# LVDS_CMOS_LVDT41v3.net
KiCad netlist of a schematic drawn in EAGLE
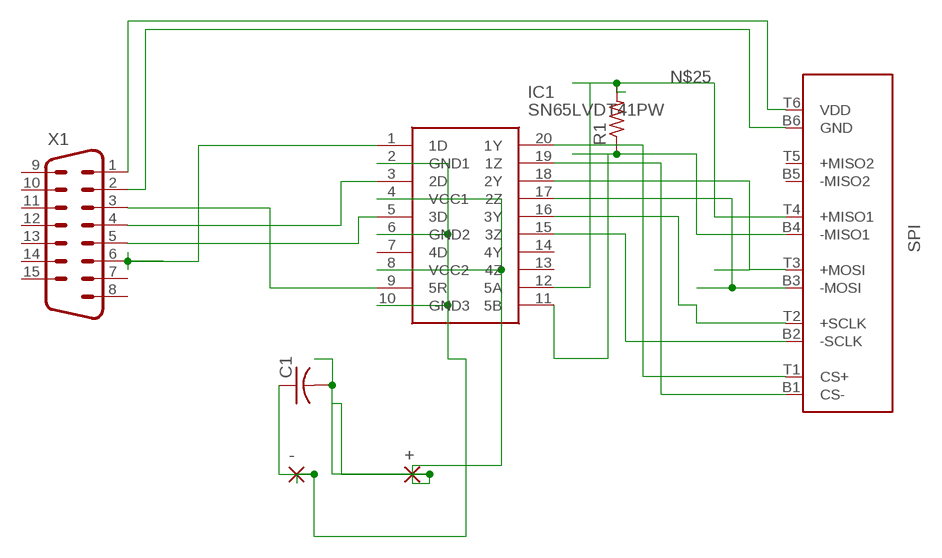
[diagram p0: schematic, sheet 1]

(export (version "E")
  (design (tool "Eeschema 10.0.6"))
  (components
    (comp (ref "+")
      (value "3,17/1,3")
      (footprint "eagle-import:3,17_1,3")
      (libsource (lib "eagle-import") (part "3,17/1,3"))
    )
    (comp (ref "-")
      (value "3,17/1,3")
      (footprint "eagle-import:3,17_1,3")
      (libsource (lib "eagle-import") (part "3,17/1,3"))
    )
    (comp (ref "C1")
      (value "C-USC0805")
      (footprint "eagle-import:C0805")
      (libsource (lib "eagle-import") (part "C-USC0805"))
    )
    (comp (ref "IC1")
      (value "SN65LVDT41PW")
      (footprint "eagle-import:SOP65P640X120-20N")
      (fields (field (name "RS_PART_NUMBER") "1625262"))
      (libsource (lib "eagle-import") (part "SN65LVDT41PW"))
    )
    (comp (ref "R1")
      (value "R-US_R0603")
      (footprint "eagle-import:R0603")
      (libsource (lib "eagle-import") (part "R-US_R0603"))
    )
    (comp (ref "SPI")
      (value "SPI")
      (footprint "eagle-import:OMNETICS_PZN-12-AA-UPDATED")
      (libsource (lib "eagle-import") (part "OMNETICS-CONNECTOR-SLAVE-SIDE"))
    )
    (comp (ref "X1")
      (value "M15H")
      (footprint "eagle-import:M15H")
      (libsource (lib "eagle-import") (part "M15H"))
    )
  )
  (nets
    (net (code "1") (name "/N$25") (class "Default")
      (node (ref "IC1") (pin "12") (pinfunction "5A_12") (pintype "input"))
      (node (ref "R1") (pin "2") (pinfunction "2_2") (pintype "passive"))
      (node (ref "SPI") (pin "T4") (pinfunction "+MISO1_T4") (pintype "bidirectional"))
    )
    (net (code "2") (name "Net-(+-P)") (class "Default")
      (node (ref "+") (pin "1") (pinfunction "P_1") (pintype "passive"))
      (node (ref "C1") (pin "2") (pinfunction "2_2") (pintype "passive"))
      (node (ref "IC1") (pin "4") (pinfunction "VCC1_4") (pintype "power_in"))
      (node (ref "IC1") (pin "8") (pinfunction "VCC2_8") (pintype "power_in"))
    )
    (net (code "3") (name "Net-(--P)") (class "Default")
      (node (ref "-") (pin "1") (pinfunction "P_1") (pintype "passive"))
      (node (ref "C1") (pin "1") (pinfunction "1_1") (pintype "passive"))
      (node (ref "IC1") (pin "10") (pinfunction "GND3_10") (pintype "power_in"))
      (node (ref "IC1") (pin "2") (pinfunction "GND1_2") (pintype "power_in"))
      (node (ref "IC1") (pin "6") (pinfunction "GND2_6") (pintype "power_in"))
    )
    (net (code "4") (name "Net-(IC1-1D)") (class "Default")
      (node (ref "IC1") (pin "1") (pinfunction "1D_1") (pintype "input"))
      (node (ref "X1") (pin "6") (pinfunction "6_6") (pintype "passive"))
    )
    (net (code "5") (name "Net-(IC1-1Y)") (class "Default")
      (node (ref "IC1") (pin "20") (pinfunction "1Y_20") (pintype "output"))
      (node (ref "SPI") (pin "T1") (pinfunction "CS+_T1") (pintype "bidirectional"))
    )
    (net (code "6") (name "Net-(IC1-1Z)") (class "Default")
      (node (ref "IC1") (pin "19") (pinfunction "1Z_19") (pintype "output"))
      (node (ref "SPI") (pin "B1") (pinfunction "CS-_B1") (pintype "bidirectional"))
    )
    (net (code "7") (name "Net-(IC1-2D)") (class "Default")
      (node (ref "IC1") (pin "3") (pinfunction "2D_3") (pintype "input"))
      (node (ref "X1") (pin "4") (pinfunction "4_4") (pintype "passive"))
    )
    (net (code "8") (name "Net-(IC1-2Y)") (class "Default")
      (node (ref "IC1") (pin "18") (pinfunction "2Y_18") (pintype "output"))
      (node (ref "SPI") (pin "T3") (pinfunction "+MOSI_T3") (pintype "bidirectional"))
    )
    (net (code "9") (name "Net-(IC1-2Z)") (class "Default")
      (node (ref "IC1") (pin "17") (pinfunction "2Z_17") (pintype "output"))
      (node (ref "SPI") (pin "B3") (pinfunction "-MOSI_B3") (pintype "bidirectional"))
    )
    (net (code "10") (name "Net-(IC1-3D)") (class "Default")
      (node (ref "IC1") (pin "5") (pinfunction "3D_5") (pintype "input"))
      (node (ref "X1") (pin "5") (pinfunction "5_5") (pintype "passive"))
    )
    (net (code "11") (name "Net-(IC1-3Y)") (class "Default")
      (node (ref "IC1") (pin "16") (pinfunction "3Y_16") (pintype "output"))
      (node (ref "SPI") (pin "T2") (pinfunction "+SCLK_T2") (pintype "bidirectional"))
    )
    (net (code "12") (name "Net-(IC1-3Z)") (class "Default")
      (node (ref "IC1") (pin "15") (pinfunction "3Z_15") (pintype "output"))
      (node (ref "SPI") (pin "B2") (pinfunction "-SCLK_B2") (pintype "bidirectional"))
    )
    (net (code "13") (name "Net-(IC1-5B)") (class "Default")
      (node (ref "IC1") (pin "11") (pinfunction "5B_11") (pintype "input"))
      (node (ref "R1") (pin "1") (pinfunction "1_1") (pintype "passive"))
      (node (ref "SPI") (pin "B4") (pinfunction "-MISO1_B4") (pintype "bidirectional"))
    )
    (net (code "14") (name "Net-(IC1-5R)") (class "Default")
      (node (ref "IC1") (pin "9") (pinfunction "5R_9") (pintype "output"))
      (node (ref "X1") (pin "3") (pinfunction "3_3") (pintype "passive"))
    )
    (net (code "15") (name "Net-(SPI-GND)") (class "Default")
      (node (ref "SPI") (pin "B6") (pinfunction "GND_B6") (pintype "bidirectional"))
      (node (ref "X1") (pin "2") (pinfunction "2_2") (pintype "passive"))
    )
    (net (code "16") (name "Net-(SPI-VDD)") (class "Default")
      (node (ref "SPI") (pin "T6") (pinfunction "VDD_T6") (pintype "bidirectional"))
      (node (ref "X1") (pin "1") (pinfunction "1_1") (pintype "passive"))
    )
    (net (code "17") (name "unconnected-(IC1-4D-Pad7)") (class "Default")
      (node (ref "IC1") (pin "7") (pinfunction "4D_7") (pintype "input"))
    )
    (net (code "18") (name "unconnected-(IC1-4Y-Pad14)") (class "Default")
      (node (ref "IC1") (pin "14") (pinfunction "4Y_14") (pintype "output"))
    )
    (net (code "19") (name "unconnected-(IC1-4Z-Pad13)") (class "Default")
      (node (ref "IC1") (pin "13") (pinfunction "4Z_13") (pintype "output"))
    )
    (net (code "20") (name "unconnected-(SPI-+MISO2-PadT5)") (class "Default")
      (node (ref "SPI") (pin "T5") (pinfunction "+MISO2_T5") (pintype "bidirectional"))
    )
    (net (code "21") (name "unconnected-(SPI--MISO2-PadB5)") (class "Default")
      (node (ref "SPI") (pin "B5") (pinfunction "-MISO2_B5") (pintype "bidirectional"))
    )
    (net (code "22") (name "unconnected-(X1-Pad7)") (class "Default")
      (node (ref "X1") (pin "7") (pinfunction "7_7") (pintype "passive"))
    )
    (net (code "23") (name "unconnected-(X1-Pad8)") (class "Default")
      (node (ref "X1") (pin "8") (pinfunction "8_8") (pintype "passive"))
    )
    (net (code "24") (name "unconnected-(X1-Pad9)") (class "Default")
      (node (ref "X1") (pin "9") (pinfunction "9_9") (pintype "passive"))
    )
    (net (code "25") (name "unconnected-(X1-Pad10)") (class "Default")
      (node (ref "X1") (pin "10") (pinfunction "10_10") (pintype "passive"))
    )
    (net (code "26") (name "unconnected-(X1-Pad11)") (class "Default")
      (node (ref "X1") (pin "11") (pinfunction "11_11") (pintype "passive"))
    )
    (net (code "27") (name "unconnected-(X1-Pad12)") (class "Default")
      (node (ref "X1") (pin "12") (pinfunction "12_12") (pintype "passive"))
    )
    (net (code "28") (name "unconnected-(X1-Pad13)") (class "Default")
      (node (ref "X1") (pin "13") (pinfunction "13_13") (pintype "passive"))
    )
    (net (code "29") (name "unconnected-(X1-Pad14)") (class "Default")
      (node (ref "X1") (pin "14") (pinfunction "14_14") (pintype "passive"))
    )
    (net (code "30") (name "unconnected-(X1-Pad15)") (class "Default")
      (node (ref "X1") (pin "15") (pinfunction "15_15") (pintype "passive"))
    )
  )
)
